# connector.net
KiCad netlist of a schematic drawn in Altium Designer
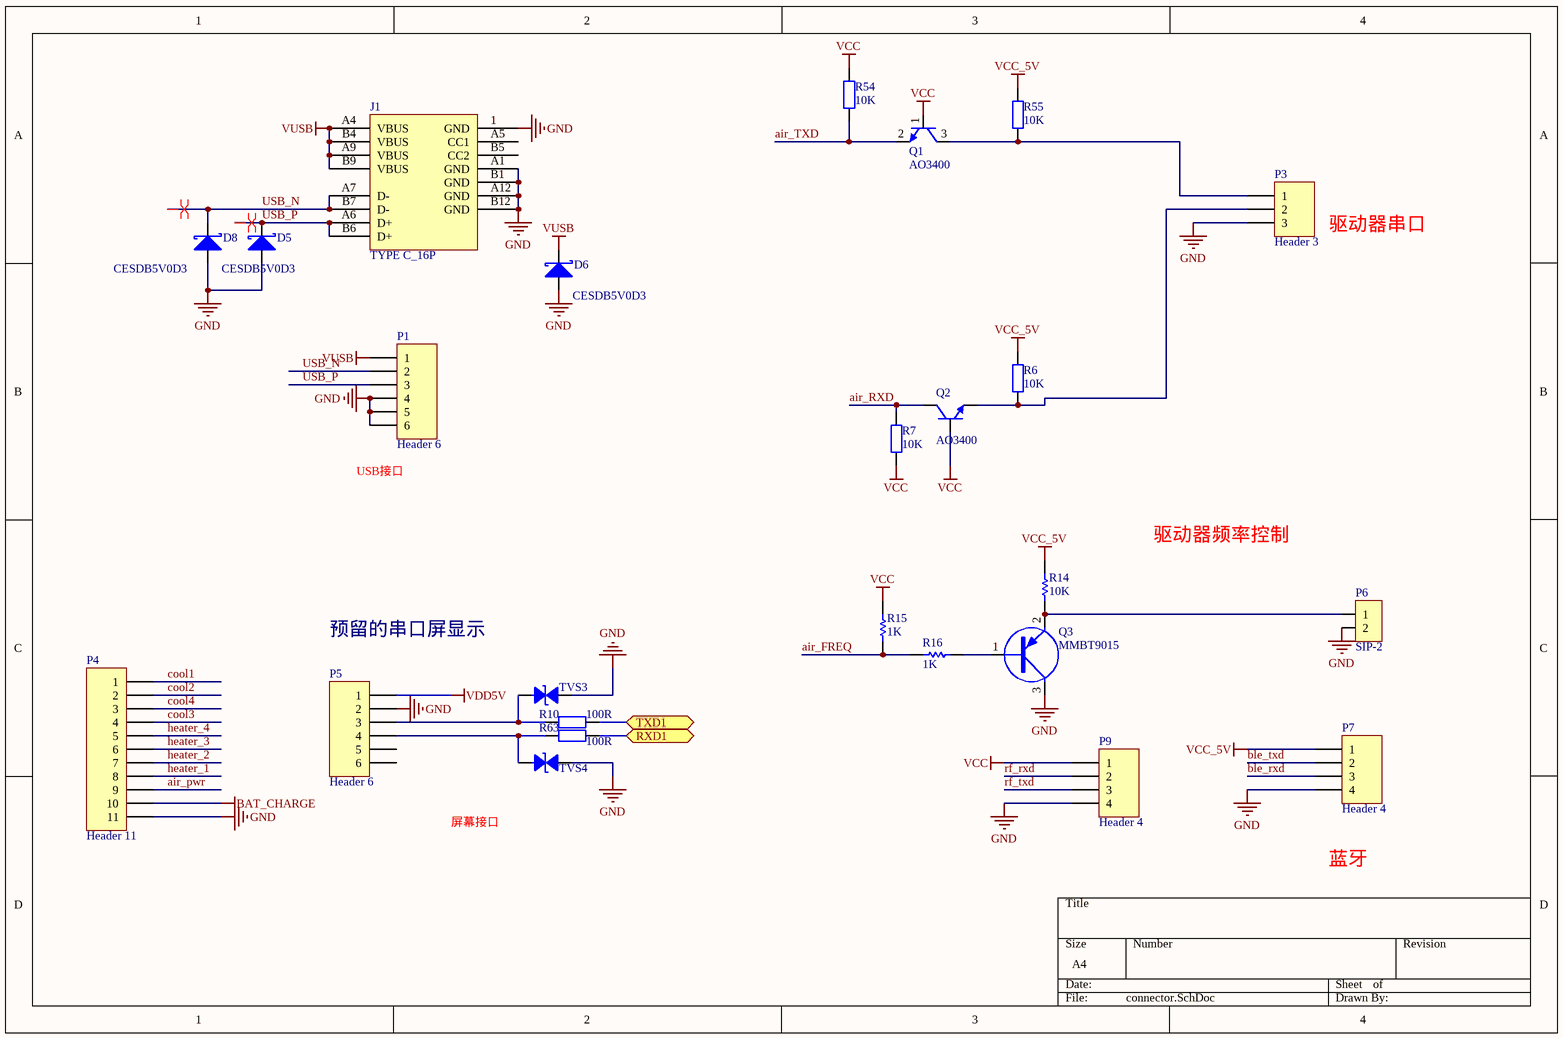
[diagram p0: connector.SchDoc]

(export (version "E")
  (design (tool "Eeschema 10.0.6"))
  (components
    (comp (ref "D5")
      (value "CESDB5V0D3")
      (footprint "SOD323")
      (description "Schottky Diode")
      (libsource (lib "*") (part "DIODE S"))
    )
    (comp (ref "D6")
      (value "CESDB5V0D3")
      (footprint "SOD323")
      (description "Schottky Diode")
      (libsource (lib "*") (part "DIODE S"))
    )
    (comp (ref "D8")
      (value "CESDB5V0D3")
      (footprint "SOD323")
      (description "Schottky Diode")
      (libsource (lib "*") (part "DIODE S"))
    )
    (comp (ref "J1")
      (value "TYPE C_16P")
      (footprint "TYPEC_16P")
      (libsource (lib "Schlib_20110825") (part "TYPE C_16P"))
    )
    (comp (ref "P1")
      (value "Header 6")
      (footprint "USB-A")
      (description "Header, 6-Pin")
      (fields (field (name "PUBLISHER") "Altium Limited"))
      (libsource (lib "") (part "Header 6_1"))
    )
    (comp (ref "P3")
      (value "Header 3")
      (footprint "3X2.54MMZ")
      (description "Header, 3-Pin")
      (fields (field (name "PUBLISHER") "Altium Limited"))
      (libsource (lib "Miscellaneous Connectors") (part "Header 3"))
    )
    (comp (ref "P4")
      (value "Header 11")
      (footprint "12X2MMZ")
      (description "Header, 11-Pin")
      (fields (field (name "PUBLISHER") "Altium Limited"))
      (libsource (lib "Miscellaneous Connectors") (part "Header 11"))
    )
    (comp (ref "P5")
      (value "Header 6")
      (footprint "6X2MMZ")
      (description "Header, 6-Pin")
      (fields (field (name "PUBLISHER") "Altium Limited"))
      (libsource (lib "Miscellaneous Connectors") (part "Header 6"))
    )
    (comp (ref "P6")
      (value "SIP-2")
      (footprint "SIP-2A")
      (description "XH2.54 2P 立贴")
      (libsource (lib "XiaoyI") (part "SIP-2"))
    )
    (comp (ref "P7")
      (value "Header 4")
      (footprint "4X2.54MMZ")
      (description "Header, 4-Pin")
      (fields (field (name "PUBLISHER") "Altium Limited"))
      (libsource (lib "Miscellaneous Connectors") (part "Header 4"))
    )
    (comp (ref "P9")
      (value "Header 4")
      (footprint "4X2.54MMZ")
      (description "Header, 4-Pin")
      (fields (field (name "PUBLISHER") "Altium Limited"))
      (libsource (lib "Miscellaneous Connectors") (part "Header 4"))
    )
    (comp (ref "Q1")
      (value "AO3400")
      (footprint "SOT-23")
      (description "NPN")
      (libsource (lib "XiaoyI") (part "NPN-1"))
    )
    (comp (ref "Q2")
      (value "AO3400")
      (footprint "SOT-23")
      (description "NPN")
      (libsource (lib "") (part "NPN-1_1"))
    )
    (comp (ref "Q3") (value "MMBT9015") (footprint "SOT23-3") (libsource (lib "Schlib1") (part "PNP")))
    (comp (ref "R6")
      (value "10K")
      (footprint "0603r")
      (description "贴片电阻 1%")
      (libsource (lib "") (part "RES2_1"))
    )
    (comp (ref "R7")
      (value "10K")
      (footprint "0603r")
      (description "贴片电阻 1%")
      (libsource (lib "") (part "RES2_1"))
    )
    (comp (ref "R10")
      (value "100R")
      (footprint "0603R")
      (description "贴片电阻 5%")
      (libsource (lib "XiaoyI") (part "RES2"))
    )
    (comp (ref "R14")
      (value "10K")
      (footprint "0603R")
      (description "Resistor")
      (fields (field (name "PUBLISHER") "Altium Limited"))
      (libsource (lib "Miscellaneous Devices") (part "Res1"))
    )
    (comp (ref "R15")
      (value "1K")
      (footprint "0603R")
      (description "Resistor")
      (fields (field (name "PUBLISHER") "Altium Limited"))
      (libsource (lib "Miscellaneous Devices") (part "Res1"))
    )
    (comp (ref "R16")
      (value "1K")
      (footprint "0603R")
      (description "Resistor")
      (fields (field (name "PUBLISHER") "Altium Limited"))
      (libsource (lib "Miscellaneous Devices") (part "Res1"))
    )
    (comp (ref "R54")
      (value "10K")
      (footprint "0603r")
      (description "贴片电阻 1%")
      (libsource (lib "") (part "RES2_1"))
    )
    (comp (ref "R55")
      (value "10K")
      (footprint "0603r")
      (description "贴片电阻 1%")
      (libsource (lib "") (part "RES2_1"))
    )
    (comp (ref "R63")
      (value "100R")
      (footprint "0603R")
      (description "贴片电阻 5%")
      (libsource (lib "XiaoyI") (part "RES2"))
    )
    (comp (ref "TVS3")
      (value "ESD5Z5.0CT1G")
      (footprint "SOD-523")
      (description "TVS")
      (libsource (lib "XiaoyI") (part "TVS-1"))
    )
    (comp (ref "TVS4")
      (value "ESD5Z5.0CT1G")
      (footprint "SOD-523")
      (description "TVS")
      (libsource (lib "XiaoyI") (part "TVS-1"))
    )
  )
  (nets
    (net (code "1") (name "/RXD1") (class "Default")
      (node (ref "R63") (pin "2") (pinfunction "2_2") (pintype "passive"))
    )
    (net (code "2") (name "/TXD1") (class "Default")
      (node (ref "R10") (pin "2") (pinfunction "2_2") (pintype "passive"))
    )
    (net (code "3") (name "/USB_N") (class "Default")
      (node (ref "D8") (pin "2") (pinfunction "K_2") (pintype "passive"))
      (node (ref "J1") (pin "A7") (pinfunction "D-_A7") (pintype "passive"))
      (node (ref "J1") (pin "B7") (pinfunction "D-_B7") (pintype "passive"))
      (node (ref "P1") (pin "2") (pinfunction "2_2") (pintype "passive"))
    )
    (net (code "4") (name "/USB_P") (class "Default")
      (node (ref "D5") (pin "2") (pinfunction "K_2") (pintype "passive"))
      (node (ref "J1") (pin "A6") (pinfunction "D+_A6") (pintype "passive"))
      (node (ref "J1") (pin "B6") (pinfunction "D+_B6") (pintype "passive"))
      (node (ref "P1") (pin "3") (pinfunction "3_3") (pintype "passive"))
    )
    (net (code "5") (name "/air_FREQ") (class "Default")
      (node (ref "R15") (pin "2") (pinfunction "2_2") (pintype "passive"))
      (node (ref "R16") (pin "2") (pinfunction "2_2") (pintype "passive"))
    )
    (net (code "6") (name "/air_RXD") (class "Default")
      (node (ref "Q2") (pin "3") (pinfunction "C_3") (pintype "passive"))
      (node (ref "R7") (pin "2") (pinfunction "2_2") (pintype "passive"))
    )
    (net (code "7") (name "/air_TXD") (class "Default")
      (node (ref "Q1") (pin "2") (pinfunction "E_2") (pintype "passive"))
      (node (ref "R54") (pin "1") (pinfunction "1_1") (pintype "passive"))
    )
    (net (code "8") (name "/air_pwr") (class "Default")
      (node (ref "P4") (pin "9") (pinfunction "9_9") (pintype "passive"))
    )
    (net (code "9") (name "/ble_rxd") (class "Default")
      (node (ref "P7") (pin "3") (pinfunction "3_3") (pintype "passive"))
    )
    (net (code "10") (name "/ble_txd") (class "Default")
      (node (ref "P7") (pin "2") (pinfunction "2_2") (pintype "passive"))
    )
    (net (code "11") (name "/cool1") (class "Default")
      (node (ref "P4") (pin "1") (pinfunction "1_1") (pintype "passive"))
    )
    (net (code "12") (name "/cool2") (class "Default")
      (node (ref "P4") (pin "2") (pinfunction "2_2") (pintype "passive"))
    )
    (net (code "13") (name "/cool3") (class "Default")
      (node (ref "P4") (pin "4") (pinfunction "4_4") (pintype "passive"))
    )
    (net (code "14") (name "/cool4") (class "Default")
      (node (ref "P4") (pin "3") (pinfunction "3_3") (pintype "passive"))
    )
    (net (code "15") (name "/heater_1") (class "Default")
      (node (ref "P4") (pin "8") (pinfunction "8_8") (pintype "passive"))
    )
    (net (code "16") (name "/heater_2") (class "Default")
      (node (ref "P4") (pin "7") (pinfunction "7_7") (pintype "passive"))
    )
    (net (code "17") (name "/heater_3") (class "Default")
      (node (ref "P4") (pin "6") (pinfunction "6_6") (pintype "passive"))
    )
    (net (code "18") (name "/heater_4") (class "Default")
      (node (ref "P4") (pin "5") (pinfunction "5_5") (pintype "passive"))
    )
    (net (code "19") (name "/rf_rxd") (class "Default")
      (node (ref "P9") (pin "2") (pinfunction "2_2") (pintype "passive"))
    )
    (net (code "20") (name "/rf_txd") (class "Default")
      (node (ref "P9") (pin "3") (pinfunction "3_3") (pintype "passive"))
    )
    (net (code "21") (name "BAT_CHARGE") (class "Default")
      (node (ref "P4") (pin "10") (pinfunction "10_10") (pintype "passive"))
    )
    (net (code "22") (name "GND") (class "Default")
      (node (ref "D5") (pin "1") (pinfunction "A_1") (pintype "passive"))
      (node (ref "D6") (pin "1") (pinfunction "A_1") (pintype "passive"))
      (node (ref "D8") (pin "1") (pinfunction "A_1") (pintype "passive"))
      (node (ref "J1") (pin "1") (pinfunction "GND_1") (pintype "passive"))
      (node (ref "J1") (pin "A1") (pinfunction "GND_A1") (pintype "passive"))
      (node (ref "J1") (pin "A12") (pinfunction "GND_A12") (pintype "passive"))
      (node (ref "J1") (pin "B1") (pinfunction "GND_B1") (pintype "passive"))
      (node (ref "J1") (pin "B12") (pinfunction "GND_B12") (pintype "passive"))
      (node (ref "P1") (pin "4") (pinfunction "4_4") (pintype "passive"))
      (node (ref "P1") (pin "5") (pinfunction "5_5") (pintype "passive"))
      (node (ref "P1") (pin "6") (pinfunction "6_6") (pintype "passive"))
      (node (ref "P3") (pin "3") (pinfunction "3_3") (pintype "passive"))
      (node (ref "P4") (pin "11") (pinfunction "11_11") (pintype "passive"))
      (node (ref "P5") (pin "2") (pinfunction "2_2") (pintype "passive"))
      (node (ref "P6") (pin "2") (pinfunction "2_2") (pintype "passive"))
      (node (ref "P7") (pin "4") (pinfunction "4_4") (pintype "passive"))
      (node (ref "P9") (pin "4") (pinfunction "4_4") (pintype "passive"))
      (node (ref "Q3") (pin "3") (pinfunction "C_3") (pintype "passive"))
      (node (ref "TVS3") (pin "1") (pinfunction "A_1") (pintype "passive"))
      (node (ref "TVS4") (pin "1") (pinfunction "A_1") (pintype "passive"))
    )
    (net (code "23") (name "Net-(Q1-C)") (class "Default")
      (node (ref "P3") (pin "1") (pinfunction "1_1") (pintype "passive"))
      (node (ref "Q1") (pin "3") (pinfunction "C_3") (pintype "passive"))
      (node (ref "R55") (pin "1") (pinfunction "1_1") (pintype "passive"))
    )
    (net (code "24") (name "Net-(Q2-E)") (class "Default")
      (node (ref "P3") (pin "2") (pinfunction "2_2") (pintype "passive"))
      (node (ref "Q2") (pin "2") (pinfunction "E_2") (pintype "passive"))
      (node (ref "R6") (pin "1") (pinfunction "1_1") (pintype "passive"))
    )
    (net (code "25") (name "Net-(Q3-B)") (class "Default")
      (node (ref "Q3") (pin "1") (pinfunction "B_1") (pintype "passive"))
      (node (ref "R16") (pin "1") (pinfunction "1_1") (pintype "passive"))
    )
    (net (code "26") (name "Net-(Q3-E)") (class "Default")
      (node (ref "P6") (pin "1") (pinfunction "1_1") (pintype "passive"))
      (node (ref "Q3") (pin "2") (pinfunction "E_2") (pintype "passive"))
      (node (ref "R14") (pin "1") (pinfunction "1_1") (pintype "passive"))
    )
    (net (code "27") (name "Net-(TVS3-B)") (class "Default")
      (node (ref "P5") (pin "3") (pinfunction "3_3") (pintype "passive"))
      (node (ref "R10") (pin "1") (pinfunction "1_1") (pintype "passive"))
      (node (ref "TVS3") (pin "2") (pinfunction "B_2") (pintype "passive"))
    )
    (net (code "28") (name "Net-(TVS4-B)") (class "Default")
      (node (ref "P5") (pin "4") (pinfunction "4_4") (pintype "passive"))
      (node (ref "R63") (pin "1") (pinfunction "1_1") (pintype "passive"))
      (node (ref "TVS4") (pin "2") (pinfunction "B_2") (pintype "passive"))
    )
    (net (code "29") (name "VCC") (class "Default")
      (node (ref "P9") (pin "1") (pinfunction "1_1") (pintype "passive"))
      (node (ref "Q1") (pin "1") (pinfunction "B_1") (pintype "passive"))
      (node (ref "Q2") (pin "1") (pinfunction "B_1") (pintype "passive"))
      (node (ref "R15") (pin "1") (pinfunction "1_1") (pintype "passive"))
      (node (ref "R54") (pin "2") (pinfunction "2_2") (pintype "passive"))
      (node (ref "R7") (pin "1") (pinfunction "1_1") (pintype "passive"))
    )
    (net (code "30") (name "VCC_5V") (class "Default")
      (node (ref "P7") (pin "1") (pinfunction "1_1") (pintype "passive"))
      (node (ref "R14") (pin "2") (pinfunction "2_2") (pintype "passive"))
      (node (ref "R55") (pin "2") (pinfunction "2_2") (pintype "passive"))
      (node (ref "R6") (pin "2") (pinfunction "2_2") (pintype "passive"))
    )
    (net (code "31") (name "VDD5V") (class "Default")
      (node (ref "P5") (pin "1") (pinfunction "1_1") (pintype "passive"))
    )
    (net (code "32") (name "VUSB") (class "Default")
      (node (ref "D6") (pin "2") (pinfunction "K_2") (pintype "passive"))
      (node (ref "J1") (pin "A4") (pinfunction "VBUS_A4") (pintype "passive"))
      (node (ref "J1") (pin "A9") (pinfunction "VBUS_A9") (pintype "passive"))
      (node (ref "J1") (pin "B4") (pinfunction "VBUS_B4") (pintype "passive"))
      (node (ref "J1") (pin "B9") (pinfunction "VBUS_B9") (pintype "passive"))
      (node (ref "P1") (pin "1") (pinfunction "1_1") (pintype "passive"))
    )
    (net (code "33") (name "unconnected-(J1-CC1-PadA5)") (class "Default")
      (node (ref "J1") (pin "A5") (pinfunction "CC1_A5") (pintype "passive"))
    )
    (net (code "34") (name "unconnected-(J1-CC2-PadB5)") (class "Default")
      (node (ref "J1") (pin "B5") (pinfunction "CC2_B5") (pintype "passive"))
    )
    (net (code "35") (name "unconnected-(P5-Pad5)") (class "Default")
      (node (ref "P5") (pin "5") (pinfunction "5_5") (pintype "passive"))
    )
    (net (code "36") (name "unconnected-(P5-Pad6)") (class "Default")
      (node (ref "P5") (pin "6") (pinfunction "6_6") (pintype "passive"))
    )
  )
)
